# ISP_Pogo_Pin_Adapter_v1.net
KiCad netlist of a schematic drawn in EAGLE
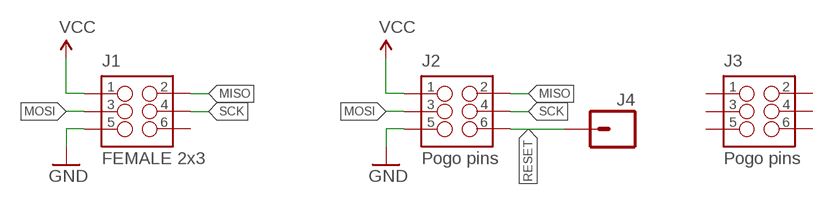
[diagram p0: schematic, sheet 1]

(export (version "E")
  (design (tool "Eeschema 10.0.6"))
  (components
    (comp (ref "J1")
      (value "FEMALE 2x3")
      (footprint "eagle-import:2X3")
      (libsource (lib "eagle-import") (part "M03X2FEMALE"))
    )
    (comp (ref "J2")
      (value "Pogo pins")
      (footprint "eagle-import:2X3_POGO")
      (libsource (lib "eagle-import") (part "M03X2POGO_PINS"))
    )
    (comp (ref "J3")
      (value "Pogo pins")
      (footprint "eagle-import:2X3_POGO")
      (libsource (lib "eagle-import") (part "M03X2POGO_PINS"))
    )
    (comp (ref "J4")
      (value "M01PTH")
      (footprint "eagle-import:1X01")
      (libsource (lib "eagle-import") (part "M01PTH"))
    )
  )
  (nets
    (net (code "1") (name "GND") (class "Default")
      (node (ref "J1") (pin "5") (pinfunction "5_5") (pintype "bidirectional"))
      (node (ref "J2") (pin "P$5") (pinfunction "5_P$5") (pintype "bidirectional"))
    )
    (net (code "2") (name "MISO") (class "Default")
      (node (ref "J1") (pin "2") (pinfunction "2_2") (pintype "bidirectional"))
      (node (ref "J2") (pin "P$2") (pinfunction "2_P$2") (pintype "bidirectional"))
    )
    (net (code "3") (name "MOSI") (class "Default")
      (node (ref "J1") (pin "3") (pinfunction "3_3") (pintype "bidirectional"))
      (node (ref "J2") (pin "P$3") (pinfunction "3_P$3") (pintype "bidirectional"))
    )
    (net (code "4") (name "RESET") (class "Default")
      (node (ref "J2") (pin "P$6") (pinfunction "6_P$6") (pintype "bidirectional"))
      (node (ref "J4") (pin "1") (pinfunction "1_1") (pintype "passive"))
    )
    (net (code "5") (name "SCK") (class "Default")
      (node (ref "J1") (pin "4") (pinfunction "4_4") (pintype "bidirectional"))
      (node (ref "J2") (pin "P$4") (pinfunction "4_P$4") (pintype "bidirectional"))
    )
    (net (code "6") (name "VCC") (class "Default")
      (node (ref "J1") (pin "1") (pinfunction "1_1") (pintype "bidirectional"))
      (node (ref "J2") (pin "P$1") (pinfunction "1_P$1") (pintype "bidirectional"))
    )
    (net (code "7") (name "unconnected-(J1-Pad6)") (class "Default")
      (node (ref "J1") (pin "6") (pinfunction "6_6") (pintype "bidirectional"))
    )
    (net (code "8") (name "unconnected-(J3-1-PadP$1)") (class "Default")
      (node (ref "J3") (pin "P$1") (pinfunction "1_P$1") (pintype "bidirectional"))
    )
    (net (code "9") (name "unconnected-(J3-2-PadP$2)") (class "Default")
      (node (ref "J3") (pin "P$2") (pinfunction "2_P$2") (pintype "bidirectional"))
    )
    (net (code "10") (name "unconnected-(J3-3-PadP$3)") (class "Default")
      (node (ref "J3") (pin "P$3") (pinfunction "3_P$3") (pintype "bidirectional"))
    )
    (net (code "11") (name "unconnected-(J3-4-PadP$4)") (class "Default")
      (node (ref "J3") (pin "P$4") (pinfunction "4_P$4") (pintype "bidirectional"))
    )
    (net (code "12") (name "unconnected-(J3-5-PadP$5)") (class "Default")
      (node (ref "J3") (pin "P$5") (pinfunction "5_P$5") (pintype "bidirectional"))
    )
    (net (code "13") (name "unconnected-(J3-6-PadP$6)") (class "Default")
      (node (ref "J3") (pin "P$6") (pinfunction "6_P$6") (pintype "bidirectional"))
    )
  )
)
